# Indicators.net
KiCad netlist of a schematic drawn in Altium Designer
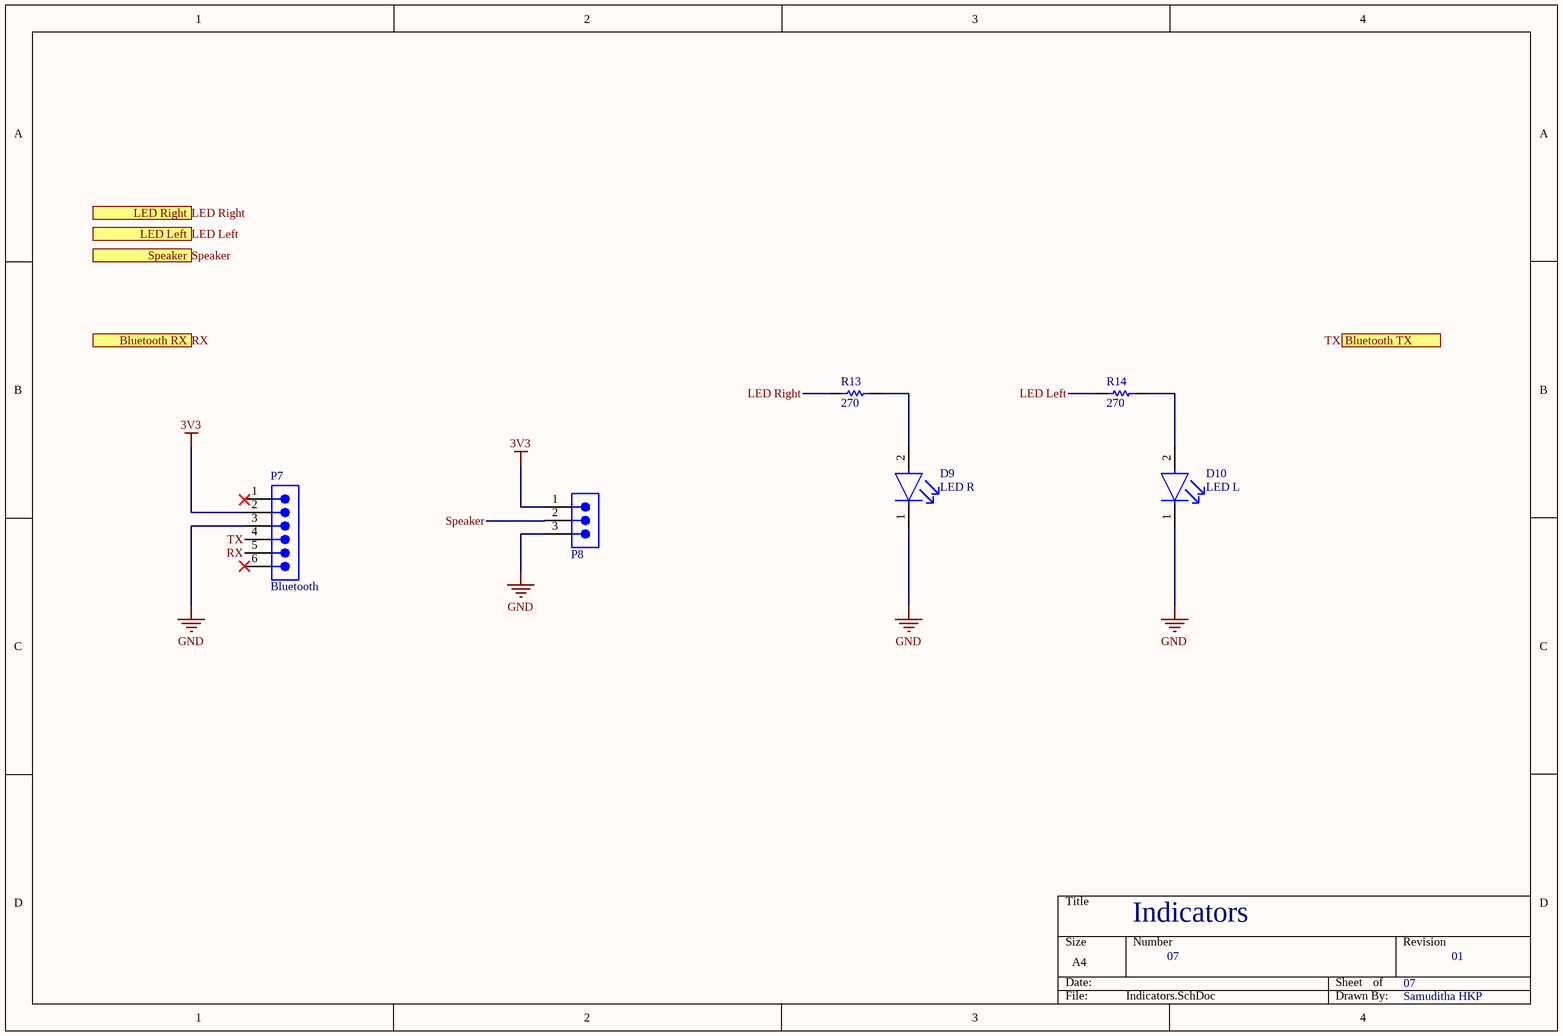
[diagram p0: Indicators.SchDoc]

(export (version "E")
  (design (tool "Eeschema 10.0.6"))
  (components
    (comp (ref "D9")
      (value "LED R")
      (footprint "FP-APHHS1005CGCK-MFG")
      (description "LED GREEN CLEAR CHIP SMD")
      (libsource (lib "Altium Content Vault") (part "8706943c75ba83719d021d2fdc84c58"))
    )
    (comp (ref "D10")
      (value "LED L")
      (footprint "FP-APHHS1005CGCK-MFG")
      (description "LED GREEN CLEAR CHIP SMD")
      (libsource (lib "Altium Content Vault") (part "8706943c75ba83719d021d2fdc84c58"))
    )
    (comp (ref "P7")
      (value "Bluetooth")
      (footprint "61300611121")
      (libsource (lib "Altium Content Vault") (part "Header_Male_1R_06P"))
    )
    (comp (ref "P8")
      (value "61300311021")
      (footprint "61300311021")
      (libsource (lib "Altium Content Vault") (part "Header_Male_1R_03P"))
    )
    (comp (ref "R13")
      (value "270")
      (footprint "RESC1005X40X25ML05T05")
      (fields (field (name "PART NUMBER") "CRCW0402270RFKED") (field (name "MANUFACTURER") "Vishay Dale"))
      (libsource (lib "Altium Content Vault") (part "RES"))
    )
    (comp (ref "R14")
      (value "270")
      (footprint "RESC1005X40X25ML05T05")
      (fields (field (name "PART NUMBER") "CRCW0402270RFKED") (field (name "MANUFACTURER") "Vishay Dale"))
      (libsource (lib "Altium Content Vault") (part "RES"))
    )
  )
  (nets
    (net (code "2") (name "/LED Left") (class "Default")
      (node (ref "R14") (pin "2") (pinfunction "2_2") (pintype "passive"))
    )
    (net (code "3") (name "/LED Right") (class "Default")
      (node (ref "R13") (pin "2") (pinfunction "2_2") (pintype "passive"))
    )
    (net (code "4") (name "/RX") (class "Default")
      (node (ref "P7") (pin "5") (pinfunction "5_5") (pintype "passive"))
    )
    (net (code "5") (name "/Speaker") (class "Default")
      (node (ref "P8") (pin "2") (pinfunction "2_2") (pintype "passive"))
    )
    (net (code "6") (name "/TX") (class "Default")
      (node (ref "P7") (pin "4") (pinfunction "4_4") (pintype "passive"))
    )
    (net (code "7") (name "3V3") (class "Default")
      (node (ref "P7") (pin "2") (pinfunction "2_2") (pintype "passive"))
      (node (ref "P8") (pin "1") (pinfunction "1_1") (pintype "passive"))
    )
    (net (code "8") (name "GND") (class "Default")
      (node (ref "D10") (pin "1") (pinfunction "C_1") (pintype "passive"))
      (node (ref "D9") (pin "1") (pinfunction "C_1") (pintype "passive"))
      (node (ref "P7") (pin "3") (pinfunction "3_3") (pintype "passive"))
      (node (ref "P8") (pin "3") (pinfunction "3_3") (pintype "passive"))
    )
    (net (code "9") (name "Net-(D9-A)") (class "Default")
      (node (ref "D9") (pin "2") (pinfunction "A_2") (pintype "passive"))
      (node (ref "R13") (pin "1") (pinfunction "1_1") (pintype "passive"))
    )
    (net (code "10") (name "Net-(D10-A)") (class "Default")
      (node (ref "D10") (pin "2") (pinfunction "A_2") (pintype "passive"))
      (node (ref "R14") (pin "1") (pinfunction "1_1") (pintype "passive"))
    )
    (net (code "11") (name "unconnected-(P7-Pad1)") (class "Default")
      (node (ref "P7") (pin "1") (pinfunction "1_1") (pintype "passive"))
    )
    (net (code "12") (name "unconnected-(P7-Pad6)") (class "Default")
      (node (ref "P7") (pin "6") (pinfunction "6_6") (pintype "passive+no_connect"))
    )
  )
)
